# MXR_MicroAmp.net
KiCad netlist of a schematic drawn in EAGLE
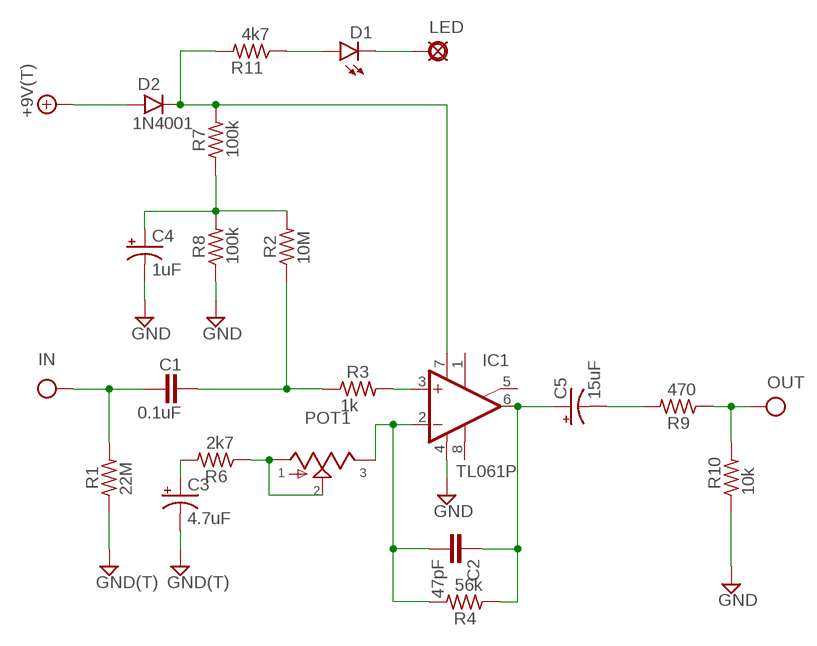
[diagram p0: schematic, sheet 1]

(export (version "E")
  (design (tool "Eeschema 10.0.6"))
  (components
    (comp (ref "+9V")
      (value "+9V(T)")
      (footprint "eagle-import:SQUARE")
      (libsource (lib "eagle-import") (part "+9V(T)"))
    )
    (comp (ref "C1")
      (value "0.1uF")
      (footprint "eagle-import:072X025")
      (libsource (lib "eagle-import") (part "072X0252"))
    )
    (comp (ref "C2")
      (value "47pF")
      (footprint "eagle-import:050X030_025")
      (libsource (lib "eagle-import") (part "050X030_0251"))
    )
    (comp (ref "C3")
      (value "4.7uF")
      (footprint "eagle-import:044A")
      (libsource (lib "eagle-import") (part "044A1"))
    )
    (comp (ref "C4")
      (value "1uF")
      (footprint "eagle-import:044A")
      (libsource (lib "eagle-import") (part "044A1"))
    )
    (comp (ref "C5")
      (value "15uF")
      (footprint "eagle-import:063_025")
      (libsource (lib "eagle-import") (part "0631"))
    )
    (comp (ref "D1")
      (value "LED3MM")
      (footprint "eagle-import:LED3MM")
      (libsource (lib "eagle-import") (part "LED3MM"))
    )
    (comp (ref "D2")
      (value "1N4001")
      (footprint "eagle-import:DO41-1")
      (libsource (lib "eagle-import") (part "1N400X.1"))
    )
    (comp (ref "G")
      (value "GND(T)")
      (footprint "eagle-import:SQUARE")
      (libsource (lib "eagle-import") (part "GND(T)"))
    )
    (comp (ref "GND")
      (value "GND(T)")
      (footprint "eagle-import:SQUARE")
      (libsource (lib "eagle-import") (part "GND(T)"))
    )
    (comp (ref "IC1")
      (value "TL061P")
      (footprint "eagle-import:DIL08")
      (libsource (lib "eagle-import") (part "TL071P"))
    )
    (comp (ref "IN")
      (value "IN(T)")
      (footprint "eagle-import:SQUARE")
      (libsource (lib "eagle-import") (part "IN(T)"))
    )
    (comp (ref "LED")
      (value "LED")
      (footprint "eagle-import:SQUARE")
      (libsource (lib "eagle-import") (part "PAD"))
    )
    (comp (ref "OUT")
      (value "OUT(T)")
      (footprint "eagle-import:SQUARE")
      (libsource (lib "eagle-import") (part "OUT(T)"))
    )
    (comp (ref "POT1")
      (value "9MMPOT_9MM_HOLES")
      (footprint "eagle-import:POT_9MM_HOLES")
      (libsource (lib "eagle-import") (part "9MMPOT_9MM_HOLES"))
    )
    (comp (ref "R1")
      (value "22M")
      (footprint "eagle-import:R0204_2")
      (libsource (lib "eagle-import") (part "3MM.2"))
    )
    (comp (ref "R2")
      (value "10M")
      (footprint "eagle-import:R0204_2")
      (libsource (lib "eagle-import") (part "3MM.2"))
    )
    (comp (ref "R3")
      (value "1k")
      (footprint "eagle-import:R0204_2")
      (libsource (lib "eagle-import") (part "3MM.2"))
    )
    (comp (ref "R4")
      (value "56k")
      (footprint "eagle-import:R0204_2")
      (libsource (lib "eagle-import") (part "3MM.2"))
    )
    (comp (ref "R6")
      (value "2k7")
      (footprint "eagle-import:R0204_2")
      (libsource (lib "eagle-import") (part "3MM.2"))
    )
    (comp (ref "R7")
      (value "100k")
      (footprint "eagle-import:R0204_2")
      (libsource (lib "eagle-import") (part "3MM.2"))
    )
    (comp (ref "R8")
      (value "100k")
      (footprint "eagle-import:R0204_2")
      (libsource (lib "eagle-import") (part "3MM.2"))
    )
    (comp (ref "R9")
      (value "470")
      (footprint "eagle-import:R0204_2")
      (libsource (lib "eagle-import") (part "3MM.2"))
    )
    (comp (ref "R10")
      (value "10k")
      (footprint "eagle-import:R0204_2")
      (libsource (lib "eagle-import") (part "3MM.2"))
    )
    (comp (ref "R11")
      (value "4k7")
      (footprint "eagle-import:R0204_2")
      (libsource (lib "eagle-import") (part "3MM.2"))
    )
  )
  (nets
    (net (code "1") (name "+9V(T)") (class "Default")
      (node (ref "+9V") (pin "1") (pinfunction "+9V_1") (pintype "power_in"))
      (node (ref "D2") (pin "A") (pinfunction "A_A") (pintype "passive"))
    )
    (net (code "2") (name "GND") (class "Default")
      (node (ref "C3") (pin "2") (pinfunction "-_2") (pintype "passive"))
      (node (ref "C4") (pin "2") (pinfunction "-_2") (pintype "passive"))
      (node (ref "G") (pin "1") (pinfunction "GND_1") (pintype "power_in"))
      (node (ref "GND") (pin "1") (pinfunction "GND_1") (pintype "power_in"))
      (node (ref "IC1") (pin "4") (pinfunction "V-_4") (pintype "power_in"))
      (node (ref "R1") (pin "1") (pinfunction "1_1") (pintype "passive"))
      (node (ref "R10") (pin "1") (pinfunction "1_1") (pintype "passive"))
      (node (ref "R8") (pin "1") (pinfunction "1_1") (pintype "passive"))
    )
    (net (code "3") (name "IN(T)") (class "Default")
      (node (ref "C1") (pin "1") (pinfunction "1_1") (pintype "passive"))
      (node (ref "IN") (pin "1") (pinfunction "IN_1") (pintype "power_in"))
      (node (ref "R1") (pin "2") (pinfunction "2_2") (pintype "passive"))
    )
    (net (code "4") (name "Net-(C1-Pad2)") (class "Default")
      (node (ref "C1") (pin "2") (pinfunction "2_2") (pintype "passive"))
      (node (ref "R2") (pin "1") (pinfunction "1_1") (pintype "passive"))
      (node (ref "R3") (pin "1") (pinfunction "1_1") (pintype "passive"))
    )
    (net (code "5") (name "Net-(C3-+)") (class "Default")
      (node (ref "C3") (pin "1") (pinfunction "+_1") (pintype "passive"))
      (node (ref "R6") (pin "2") (pinfunction "2_2") (pintype "passive"))
    )
    (net (code "6") (name "Net-(C4-+)") (class "Default")
      (node (ref "C4") (pin "1") (pinfunction "+_1") (pintype "passive"))
      (node (ref "R2") (pin "2") (pinfunction "2_2") (pintype "passive"))
      (node (ref "R7") (pin "1") (pinfunction "1_1") (pintype "passive"))
      (node (ref "R8") (pin "2") (pinfunction "2_2") (pintype "passive"))
    )
    (net (code "7") (name "Net-(C5-Pad-)") (class "Default")
      (node (ref "C5") (pin "-") (pinfunction "-_-") (pintype "passive"))
      (node (ref "R9") (pin "2") (pinfunction "2_2") (pintype "passive"))
    )
    (net (code "8") (name "Net-(D1-C)") (class "Default")
      (node (ref "D1") (pin "K") (pinfunction "C_K") (pintype "passive"))
      (node (ref "LED") (pin "1") (pinfunction "PAD_1") (pintype "passive"))
    )
    (net (code "9") (name "Net-(D1-PadA)") (class "Default")
      (node (ref "D1") (pin "A") (pinfunction "A_A") (pintype "passive"))
      (node (ref "R11") (pin "1") (pinfunction "1_1") (pintype "passive"))
    )
    (net (code "10") (name "Net-(IC1-+IN)") (class "Default")
      (node (ref "IC1") (pin "3") (pinfunction "+IN_3") (pintype "input"))
      (node (ref "R3") (pin "2") (pinfunction "2_2") (pintype "passive"))
    )
    (net (code "11") (name "Net-(IC1--IN)") (class "Default")
      (node (ref "C2") (pin "2") (pinfunction "2_2") (pintype "passive"))
      (node (ref "IC1") (pin "2") (pinfunction "-IN_2") (pintype "input"))
      (node (ref "POT1") (pin "P$3") (pinfunction "P$3_P$3") (pintype "bidirectional"))
      (node (ref "R4") (pin "2") (pinfunction "2_2") (pintype "passive"))
    )
    (net (code "12") (name "Net-(IC1-OUT)") (class "Default")
      (node (ref "C2") (pin "1") (pinfunction "1_1") (pintype "passive"))
      (node (ref "C5") (pin "+") (pinfunction "+_+") (pintype "passive"))
      (node (ref "IC1") (pin "6") (pinfunction "OUT_6") (pintype "output"))
      (node (ref "R4") (pin "1") (pinfunction "1_1") (pintype "passive"))
    )
    (net (code "13") (name "Net-(IC1-V+)") (class "Default")
      (node (ref "D2") (pin "C") (pinfunction "C_C") (pintype "passive"))
      (node (ref "IC1") (pin "7") (pinfunction "V+_7") (pintype "power_in"))
      (node (ref "R11") (pin "2") (pinfunction "2_2") (pintype "passive"))
      (node (ref "R7") (pin "2") (pinfunction "2_2") (pintype "passive"))
    )
    (net (code "14") (name "Net-(POT1-PadP$1)") (class "Default")
      (node (ref "POT1") (pin "P$1") (pinfunction "P$1_P$1") (pintype "bidirectional"))
      (node (ref "POT1") (pin "P$2") (pinfunction "P$2_P$2") (pintype "bidirectional"))
      (node (ref "R6") (pin "1") (pinfunction "1_1") (pintype "passive"))
    )
    (net (code "15") (name "OUT(T)") (class "Default")
      (node (ref "OUT") (pin "1") (pinfunction "OUT_1") (pintype "power_in"))
      (node (ref "R10") (pin "2") (pinfunction "2_2") (pintype "passive"))
      (node (ref "R9") (pin "1") (pinfunction "1_1") (pintype "passive"))
    )
    (net (code "16") (name "unconnected-(IC1-ON1-Pad1)") (class "Default")
      (node (ref "IC1") (pin "1") (pinfunction "ON1_1") (pintype "passive"))
    )
    (net (code "17") (name "unconnected-(IC1-ON2-Pad5)") (class "Default")
      (node (ref "IC1") (pin "5") (pinfunction "ON2_5") (pintype "passive"))
    )
    (net (code "18") (name "unconnected-(IC1-OPT-Pad8)") (class "Default")
      (node (ref "IC1") (pin "8") (pinfunction "OPT_8") (pintype "passive"))
    )
  )
)
